# AP_CAPSTONE.net
KiCad netlist of a schematic drawn in EAGLE
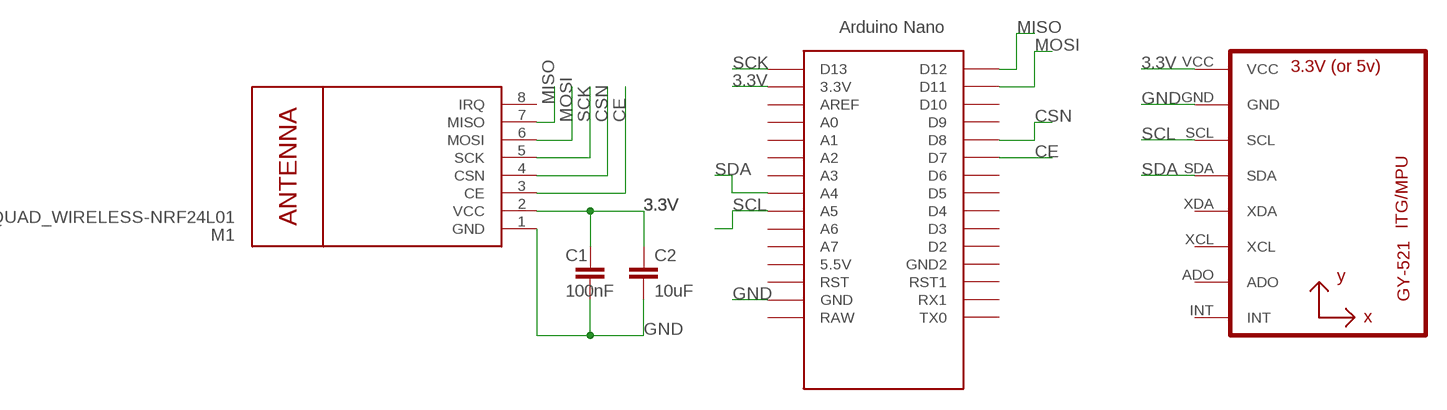
[diagram p0: schematic, sheet 1]

(export (version "E")
  (design (tool "Eeschema 10.0.6"))
  (components
    (comp (ref "C1")
      (value "100nF")
      (footprint "eagle-import:RCL_C1206")
      (libsource (lib "eagle-import") (part "RCL_C-EUC1206"))
    )
    (comp (ref "C2")
      (value "10uF")
      (footprint "eagle-import:RCL_C1206")
      (libsource (lib "eagle-import") (part "RCL_C-EUC1206"))
    )
    (comp (ref "M1")
      (value "QUAD_WIRELESS-NRF24L01")
      (footprint "eagle-import:QUAD_WIRELESS-NRF24L01")
      (libsource (lib "eagle-import") (part "QUAD_WIRELESS-NRF24L01"))
    )
    (comp (ref "U$1")
      (value "ARDUINO-CLONE_NANO")
      (footprint "eagle-import:ARDUINO-CLONE_NANO")
      (libsource (lib "eagle-import") (part "ARDUINO-CLONE_NANO"))
    )
    (comp (ref "U1")
      (value "QUAD_GY-521MPU6050")
      (footprint "eagle-import:QUAD_GY-521")
      (libsource (lib "eagle-import") (part "QUAD_GY-521MPU6050"))
    )
  )
  (nets
    (net (code "1") (name "/3.3V") (class "Default")
      (node (ref "C1") (pin "1") (pinfunction "1_1") (pintype "passive"))
      (node (ref "C2") (pin "1") (pinfunction "1_1") (pintype "passive"))
      (node (ref "M1") (pin "2") (pinfunction "VCC_2") (pintype "power_in"))
      (node (ref "U$1") (pin "3.3V") (pinfunction "3.3V_3.3V") (pintype "bidirectional"))
      (node (ref "U1") (pin "VCC") (pinfunction "VCC_VCC") (pintype "bidirectional"))
    )
    (net (code "2") (name "/CE") (class "Default")
      (node (ref "M1") (pin "3") (pinfunction "CE_3") (pintype "bidirectional"))
      (node (ref "U$1") (pin "D7") (pinfunction "D7_D7") (pintype "bidirectional"))
    )
    (net (code "3") (name "/CSN") (class "Default")
      (node (ref "M1") (pin "4") (pinfunction "CSN_4") (pintype "bidirectional"))
      (node (ref "U$1") (pin "D8") (pinfunction "D8_D8") (pintype "bidirectional"))
    )
    (net (code "4") (name "/GND") (class "Default")
      (node (ref "C1") (pin "2") (pinfunction "2_2") (pintype "passive"))
      (node (ref "C2") (pin "2") (pinfunction "2_2") (pintype "passive"))
      (node (ref "M1") (pin "1") (pinfunction "GND_1") (pintype "power_in"))
      (node (ref "U$1") (pin "GND") (pinfunction "GND_GND") (pintype "bidirectional"))
      (node (ref "U1") (pin "GND") (pinfunction "GND_GND") (pintype "bidirectional"))
    )
    (net (code "5") (name "/MISO") (class "Default")
      (node (ref "M1") (pin "7") (pinfunction "MISO_7") (pintype "bidirectional"))
      (node (ref "U$1") (pin "D12") (pinfunction "D12_D12") (pintype "bidirectional"))
    )
    (net (code "6") (name "/MOSI") (class "Default")
      (node (ref "M1") (pin "6") (pinfunction "MOSI_6") (pintype "bidirectional"))
      (node (ref "U$1") (pin "D11") (pinfunction "D11_D11") (pintype "bidirectional"))
    )
    (net (code "7") (name "/SCK") (class "Default")
      (node (ref "M1") (pin "5") (pinfunction "SCK_5") (pintype "bidirectional"))
      (node (ref "U$1") (pin "D13") (pinfunction "D13_D13") (pintype "bidirectional"))
    )
    (net (code "8") (name "/SCL") (class "Default")
      (node (ref "U$1") (pin "A5") (pinfunction "A5_A5") (pintype "bidirectional"))
      (node (ref "U1") (pin "SCL") (pinfunction "SCL_SCL") (pintype "bidirectional"))
    )
    (net (code "9") (name "/SDA") (class "Default")
      (node (ref "U$1") (pin "A4") (pinfunction "A4_A4") (pintype "bidirectional"))
      (node (ref "U1") (pin "SDA") (pinfunction "SDA_SDA") (pintype "bidirectional"))
    )
    (net (code "10") (name "unconnected-(M1-IRQ-Pad8)") (class "Default")
      (node (ref "M1") (pin "8") (pinfunction "IRQ_8") (pintype "bidirectional"))
    )
    (net (code "11") (name "unconnected-(U$1-5.5V-Pad5V)") (class "Default")
      (node (ref "U$1") (pin "5V") (pinfunction "5.5V_5V") (pintype "bidirectional"))
    )
    (net (code "12") (name "unconnected-(U$1-GND2-PadGND1)") (class "Default")
      (node (ref "U$1") (pin "GND1") (pinfunction "GND2_GND1") (pintype "bidirectional"))
    )
    (net (code "13") (name "unconnected-(U$1-PadA0)") (class "Default")
      (node (ref "U$1") (pin "A0") (pinfunction "A0_A0") (pintype "bidirectional"))
    )
    (net (code "14") (name "unconnected-(U$1-PadA1)") (class "Default")
      (node (ref "U$1") (pin "A1") (pinfunction "A1_A1") (pintype "bidirectional"))
    )
    (net (code "15") (name "unconnected-(U$1-PadA2)") (class "Default")
      (node (ref "U$1") (pin "A2") (pinfunction "A2_A2") (pintype "bidirectional"))
    )
    (net (code "16") (name "unconnected-(U$1-PadA3)") (class "Default")
      (node (ref "U$1") (pin "A3") (pinfunction "A3_A3") (pintype "bidirectional"))
    )
    (net (code "17") (name "unconnected-(U$1-PadA6)") (class "Default")
      (node (ref "U$1") (pin "A6") (pinfunction "A6_A6") (pintype "bidirectional"))
    )
    (net (code "18") (name "unconnected-(U$1-PadA7)") (class "Default")
      (node (ref "U$1") (pin "A7") (pinfunction "A7_A7") (pintype "bidirectional"))
    )
    (net (code "19") (name "unconnected-(U$1-PadAREF)") (class "Default")
      (node (ref "U$1") (pin "AREF") (pinfunction "AREF_AREF") (pintype "bidirectional"))
    )
    (net (code "20") (name "unconnected-(U$1-PadD2)") (class "Default")
      (node (ref "U$1") (pin "D2") (pinfunction "D2_D2") (pintype "bidirectional"))
    )
    (net (code "21") (name "unconnected-(U$1-PadD3)") (class "Default")
      (node (ref "U$1") (pin "D3") (pinfunction "D3_D3") (pintype "bidirectional"))
    )
    (net (code "22") (name "unconnected-(U$1-PadD4)") (class "Default")
      (node (ref "U$1") (pin "D4") (pinfunction "D4_D4") (pintype "bidirectional"))
    )
    (net (code "23") (name "unconnected-(U$1-PadD5)") (class "Default")
      (node (ref "U$1") (pin "D5") (pinfunction "D5_D5") (pintype "bidirectional"))
    )
    (net (code "24") (name "unconnected-(U$1-PadD6)") (class "Default")
      (node (ref "U$1") (pin "D6") (pinfunction "D6_D6") (pintype "bidirectional"))
    )
    (net (code "25") (name "unconnected-(U$1-PadD9)") (class "Default")
      (node (ref "U$1") (pin "D9") (pinfunction "D9_D9") (pintype "bidirectional"))
    )
    (net (code "26") (name "unconnected-(U$1-PadD10)") (class "Default")
      (node (ref "U$1") (pin "D10") (pinfunction "D10_D10") (pintype "bidirectional"))
    )
    (net (code "27") (name "unconnected-(U$1-PadICSP1)") (class "Default")
      (node (ref "U$1") (pin "ICSP1") (pinfunction "ICSP1_ICSP1") (pintype "bidirectional"))
    )
    (net (code "28") (name "unconnected-(U$1-PadICSP2)") (class "Default")
      (node (ref "U$1") (pin "ICSP2") (pinfunction "ICSP2_ICSP2") (pintype "bidirectional"))
    )
    (net (code "29") (name "unconnected-(U$1-PadICSP3)") (class "Default")
      (node (ref "U$1") (pin "ICSP3") (pinfunction "ICSP3_ICSP3") (pintype "bidirectional"))
    )
    (net (code "30") (name "unconnected-(U$1-PadICSP4)") (class "Default")
      (node (ref "U$1") (pin "ICSP4") (pinfunction "ICSP4_ICSP4") (pintype "bidirectional"))
    )
    (net (code "31") (name "unconnected-(U$1-PadICSP5)") (class "Default")
      (node (ref "U$1") (pin "ICSP5") (pinfunction "ICSP5_ICSP5") (pintype "bidirectional"))
    )
    (net (code "32") (name "unconnected-(U$1-PadICSP6)") (class "Default")
      (node (ref "U$1") (pin "ICSP6") (pinfunction "ICSP6_ICSP6") (pintype "bidirectional"))
    )
    (net (code "33") (name "unconnected-(U$1-PadRAW)") (class "Default")
      (node (ref "U$1") (pin "RAW") (pinfunction "RAW_RAW") (pintype "bidirectional"))
    )
    (net (code "34") (name "unconnected-(U$1-PadRST)") (class "Default")
      (node (ref "U$1") (pin "RST") (pinfunction "RST_RST") (pintype "bidirectional"))
    )
    (net (code "35") (name "unconnected-(U$1-PadRST1)") (class "Default")
      (node (ref "U$1") (pin "RST1") (pinfunction "RST1_RST1") (pintype "bidirectional"))
    )
    (net (code "36") (name "unconnected-(U$1-PadRX1)") (class "Default")
      (node (ref "U$1") (pin "RX1") (pinfunction "RX1_RX1") (pintype "bidirectional"))
    )
    (net (code "37") (name "unconnected-(U$1-PadTX0)") (class "Default")
      (node (ref "U$1") (pin "TX0") (pinfunction "TX0_TX0") (pintype "bidirectional"))
    )
    (net (code "38") (name "unconnected-(U1-PadADO)") (class "Default")
      (node (ref "U1") (pin "ADO") (pinfunction "ADO_ADO") (pintype "bidirectional"))
    )
    (net (code "39") (name "unconnected-(U1-PadINT)") (class "Default")
      (node (ref "U1") (pin "INT") (pinfunction "INT_INT") (pintype "bidirectional"))
    )
    (net (code "40") (name "unconnected-(U1-PadXCL)") (class "Default")
      (node (ref "U1") (pin "XCL") (pinfunction "XCL_XCL") (pintype "bidirectional"))
    )
    (net (code "41") (name "unconnected-(U1-PadXDA)") (class "Default")
      (node (ref "U1") (pin "XDA") (pinfunction "XDA_XDA") (pintype "bidirectional"))
    )
  )
)
